# settings.net
KiCad netlist of a schematic drawn in EAGLE
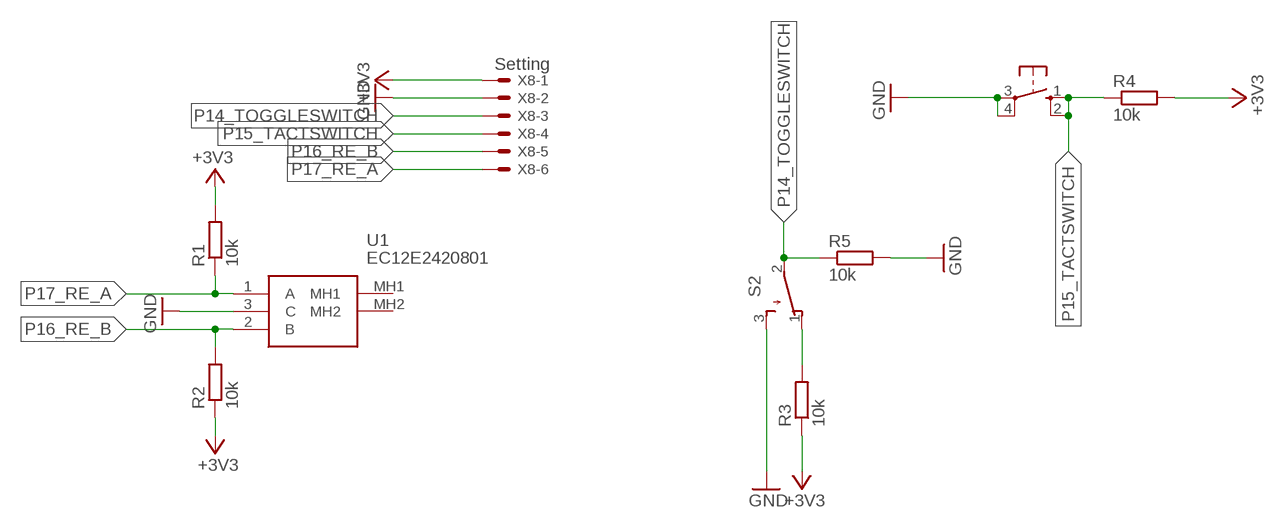
[diagram p0: schematic, sheet 1]

(export (version "E")
  (design (tool "Eeschema 10.0.6"))
  (components
    (comp (ref "R1")
      (value "10k")
      (footprint "eagle-import:R0603")
      (libsource (lib "eagle-import") (part "R-EU_R0603"))
    )
    (comp (ref "R2")
      (value "10k")
      (footprint "eagle-import:R0603")
      (libsource (lib "eagle-import") (part "R-EU_R0603"))
    )
    (comp (ref "R3")
      (value "10k")
      (footprint "eagle-import:R0603")
      (libsource (lib "eagle-import") (part "R-EU_R0603"))
    )
    (comp (ref "R4")
      (value "10k")
      (footprint "eagle-import:R0603")
      (libsource (lib "eagle-import") (part "R-EU_R0603"))
    )
    (comp (ref "R5")
      (value "10k")
      (footprint "eagle-import:R0603")
      (libsource (lib "eagle-import") (part "R-EU_R0603"))
    )
    (comp (ref "S1")
      (value "40-XX")
      (footprint "eagle-import:B3F-40XX")
      (fields (field (name "MF") "OMRON COMPONENTS USA") (field (name "MPN") "B3F-4000"))
      (libsource (lib "eagle-import") (part "40-XX"))
    )
    (comp (ref "S2")
      (value "TL32PO")
      (footprint "eagle-import:TL3XPO")
      (libsource (lib "eagle-import") (part "TL32PO"))
    )
    (comp (ref "U1")
      (value "EC12E2420801")
      (footprint "eagle-import:EC12E2420801")
      (fields (field (name "RS_PART_NUMBER") "7295836"))
      (libsource (lib "eagle-import") (part "EC12E2420801"))
    )
    (comp (ref "X8")
      (value "Setting")
      (footprint "eagle-import:JST-XH-06-PACKAGE-ROUND-PAD")
      (libsource (lib "eagle-import") (part "JST-XH-06-PIN-ROUND-PAD"))
    )
  )
  (nets
    (net (code "1") (name "+3V3") (class "Default")
      (node (ref "R1") (pin "2") (pinfunction "2_2") (pintype "passive"))
      (node (ref "R2") (pin "1") (pinfunction "1_1") (pintype "passive"))
      (node (ref "R3") (pin "1") (pinfunction "1_1") (pintype "passive"))
      (node (ref "R4") (pin "2") (pinfunction "2_2") (pintype "passive"))
      (node (ref "X8") (pin "1") (pinfunction "S_1") (pintype "passive"))
    )
    (net (code "2") (name "GND") (class "Default")
      (node (ref "R5") (pin "2") (pinfunction "2_2") (pintype "passive"))
      (node (ref "S1") (pin "3") (pinfunction "P_3") (pintype "passive"))
      (node (ref "S1") (pin "4") (pinfunction "P1_4") (pintype "passive"))
      (node (ref "S2") (pin "3") (pinfunction "S_3") (pintype "passive"))
      (node (ref "U1") (pin "3") (pinfunction "C_3") (pintype "bidirectional"))
      (node (ref "X8") (pin "2") (pinfunction "S_2") (pintype "passive"))
    )
    (net (code "3") (name "Net-(S2-O)") (class "Default")
      (node (ref "R3") (pin "2") (pinfunction "2_2") (pintype "passive"))
      (node (ref "S2") (pin "1") (pinfunction "O_1") (pintype "passive"))
    )
    (net (code "4") (name "P14_TOGGLESWITCH") (class "Default")
      (node (ref "R5") (pin "1") (pinfunction "1_1") (pintype "passive"))
      (node (ref "S2") (pin "2") (pinfunction "P_2") (pintype "passive"))
      (node (ref "X8") (pin "3") (pinfunction "S_3") (pintype "passive"))
    )
    (net (code "5") (name "P15_TACTSWITCH") (class "Default")
      (node (ref "R4") (pin "1") (pinfunction "1_1") (pintype "passive"))
      (node (ref "S1") (pin "1") (pinfunction "S_1") (pintype "passive"))
      (node (ref "S1") (pin "2") (pinfunction "S1_2") (pintype "passive"))
      (node (ref "X8") (pin "4") (pinfunction "S_4") (pintype "passive"))
    )
    (net (code "6") (name "P16_RE_B") (class "Default")
      (node (ref "R2") (pin "2") (pinfunction "2_2") (pintype "passive"))
      (node (ref "U1") (pin "2") (pinfunction "B_2") (pintype "bidirectional"))
      (node (ref "X8") (pin "5") (pinfunction "S_5") (pintype "passive"))
    )
    (net (code "7") (name "P17_RE_A") (class "Default")
      (node (ref "R1") (pin "1") (pinfunction "1_1") (pintype "passive"))
      (node (ref "U1") (pin "1") (pinfunction "A_1") (pintype "bidirectional"))
      (node (ref "X8") (pin "6") (pinfunction "S_6") (pintype "passive"))
    )
    (net (code "8") (name "unconnected-(U1-PadMH1)") (class "Default")
      (node (ref "U1") (pin "MH1") (pinfunction "MH1_MH1") (pintype "bidirectional"))
    )
    (net (code "9") (name "unconnected-(U1-PadMH2)") (class "Default")
      (node (ref "U1") (pin "MH2") (pinfunction "MH2_MH2") (pintype "bidirectional"))
    )
  )
)
